# RF.net
KiCad netlist of a schematic drawn in Altium Designer
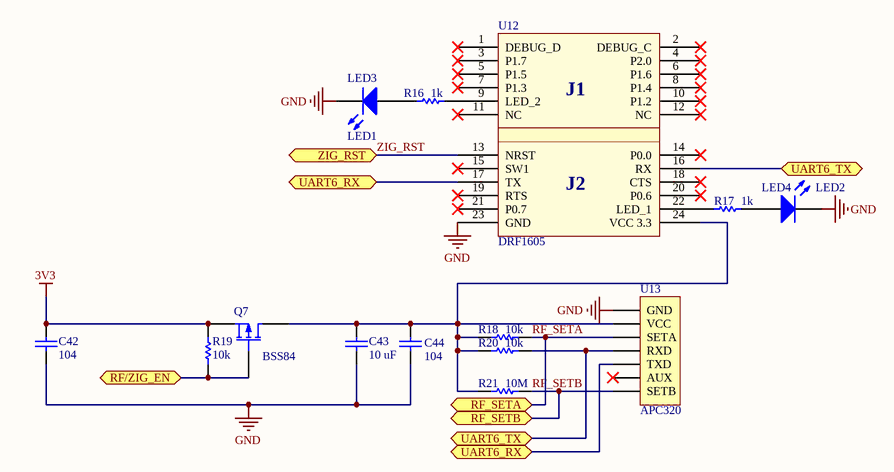
[diagram p0: RF.SchDoc]

(export (version "E")
  (design (tool "Eeschema 10.0.6"))
  (components
    (comp (ref "C42")
      (value "104")
      (footprint "C0603")
      (description "CAP CER 0.1UF 16V Y5V 0402")
      (fields
        (field (name "MANUFACTURER") "Yageo")
        (field (name "DIGI-KEY PART NUMBER") "311-1047-1-ND")
        (field (name "PUBLISHER") "Altium Limited")
      )
      (libsource (lib "RobotClub") (part "Cap_SMT"))
    )
    (comp (ref "C43")
      (value "10 uF")
      (footprint "C1210")
      (description "CAP CER 0.1UF 16V Y5V 0402")
      (fields
        (field (name "MANUFACTURER") "Yageo")
        (field (name "DIGI-KEY PART NUMBER") "311-1047-1-ND")
        (field (name "PUBLISHER") "Altium Limited")
      )
      (libsource (lib "RobotClub") (part "Cap_SMT"))
    )
    (comp (ref "C44")
      (value "104")
      (footprint "C0603")
      (description "CAP CER 0.1UF 16V Y5V 0402")
      (fields
        (field (name "MANUFACTURER") "Yageo")
        (field (name "DIGI-KEY PART NUMBER") "311-1047-1-ND")
        (field (name "PUBLISHER") "Altium Limited")
      )
      (libsource (lib "RobotClub") (part "Cap_SMT"))
    )
    (comp (ref "LED3")
      (value "LED1")
      (footprint "SM/LED_0603")
      (description "LED GREEN 0.2MM 13MCD 0402 SMD")
      (fields
        (field (name "DIGI-KEY PART NUMBER") "511-1592-2-ND")
        (field (name "MANUFACTURER") "Lite-On Inc")
        (field (name "PUBLISHER") "Altium Limited")
      )
      (libsource (lib "RobotClub") (part "LED"))
    )
    (comp (ref "LED4")
      (value "LED2")
      (footprint "SM/LED_0603")
      (description "LED GREEN 0.2MM 13MCD 0402 SMD")
      (fields
        (field (name "DIGI-KEY PART NUMBER") "511-1592-2-ND")
        (field (name "MANUFACTURER") "Lite-On Inc")
        (field (name "PUBLISHER") "Altium Limited")
      )
      (libsource (lib "RobotClub") (part "LED"))
    )
    (comp (ref "Q7")
      (value "BSS84")
      (footprint "SOT23-3")
      (description "MOSFET P-CH 50V 130MA SOT23-3")
      (fields
        (field (name "DIGI-KEY PART NUMBER") "BSS84-FDITR-ND")
        (field (name "MANUFACTURER") "Diodes Inc")
        (field (name "PUBLISHER") "Altium Limited")
      )
      (libsource (lib "RobotClub") (part "MOSFET-P GSD"))
    )
    (comp (ref "R16")
      (value "1k")
      (footprint "R0603")
      (description "Resistor SMD 5%")
      (fields
        (field (name "DIGI-KEY PART NUMBER") "P3.24KLTR-ND")
        (field (name "MANUFACTURER") "Panasonic Electronic Components")
        (field (name "PUBLISHER") "Altium Limited")
      )
      (libsource (lib "RobotClub") (part "R_SMD5"))
    )
    (comp (ref "R17")
      (value "1k")
      (footprint "R0603")
      (description "Resistor SMD 5%")
      (fields
        (field (name "DIGI-KEY PART NUMBER") "P3.24KLTR-ND")
        (field (name "MANUFACTURER") "Panasonic Electronic Components")
        (field (name "PUBLISHER") "Altium Limited")
      )
      (libsource (lib "RobotClub") (part "R_SMD5"))
    )
    (comp (ref "R18")
      (value "10k")
      (footprint "R0603")
      (description "Resistor SMD 5%")
      (fields
        (field (name "DIGI-KEY PART NUMBER") "P3.24KLTR-ND")
        (field (name "MANUFACTURER") "Panasonic Electronic Components")
        (field (name "PUBLISHER") "Altium Limited")
      )
      (libsource (lib "RobotClub") (part "R_SMD5"))
    )
    (comp (ref "R19")
      (value "10k")
      (footprint "R0603")
      (description "Resistor SMD 5%")
      (fields
        (field (name "DIGI-KEY PART NUMBER") "P3.24KLTR-ND")
        (field (name "MANUFACTURER") "Panasonic Electronic Components")
        (field (name "PUBLISHER") "Altium Limited")
      )
      (libsource (lib "RobotClub") (part "R_SMD5"))
    )
    (comp (ref "R20")
      (value "10k")
      (footprint "R0603")
      (description "Resistor SMD 5%")
      (fields
        (field (name "DIGI-KEY PART NUMBER") "P3.24KLTR-ND")
        (field (name "MANUFACTURER") "Panasonic Electronic Components")
        (field (name "PUBLISHER") "Altium Limited")
      )
      (libsource (lib "RobotClub") (part "R_SMD5"))
    )
    (comp (ref "R21")
      (value "10M")
      (footprint "R0603")
      (description "Resistor SMD 5%")
      (fields
        (field (name "DIGI-KEY PART NUMBER") "P3.24KLTR-ND")
        (field (name "MANUFACTURER") "Panasonic Electronic Components")
        (field (name "PUBLISHER") "Altium Limited")
      )
      (libsource (lib "RobotClub") (part "R_SMD5"))
    )
    (comp (ref "U12") (value "DRF1605") (footprint "DRF1605") (libsource (lib "RobotClub") (part "DRF1605")))
    (comp (ref "U13")
      (value "APC320")
      (footprint "APC320 - 2D")
      (libsource (lib "RobotClub") (part "APC320"))
    )
  )
  (nets
    (net (code "1") (name "/RF_SETA") (class "Default")
      (node (ref "R18") (pin "2") (pinfunction "2_2") (pintype "passive"))
      (node (ref "U13") (pin "3") (pinfunction "SETA_3") (pintype "passive"))
    )
    (net (code "2") (name "/RF_SETB") (class "Default")
      (node (ref "R21") (pin "2") (pinfunction "2_2") (pintype "passive"))
      (node (ref "U13") (pin "7") (pinfunction "SETB_7") (pintype "passive"))
    )
    (net (code "3") (name "/RF{slash}ZIG_EN") (class "Default")
      (node (ref "Q7") (pin "1") (pinfunction "G_1") (pintype "passive"))
      (node (ref "R19") (pin "2") (pinfunction "2_2") (pintype "passive"))
    )
    (net (code "4") (name "/UART6_RX") (class "Default")
      (node (ref "U12") (pin "17") (pinfunction "TX_17") (pintype "passive"))
      (node (ref "U13") (pin "5") (pinfunction "TXD_5") (pintype "passive"))
    )
    (net (code "5") (name "/UART6_TX") (class "Default")
      (node (ref "R20") (pin "2") (pinfunction "2_2") (pintype "passive"))
      (node (ref "U12") (pin "16") (pinfunction "RX_16") (pintype "passive"))
      (node (ref "U13") (pin "4") (pinfunction "RXD_4") (pintype "passive"))
    )
    (net (code "6") (name "/ZIG_RST") (class "Default")
      (node (ref "U12") (pin "13") (pinfunction "NRST_13") (pintype "passive"))
    )
    (net (code "7") (name "3V3") (class "Default")
      (node (ref "C42") (pin "2") (pinfunction "2_2") (pintype "passive"))
      (node (ref "Q7") (pin "2") (pinfunction "S_2") (pintype "passive"))
      (node (ref "R19") (pin "1") (pinfunction "1_1") (pintype "passive"))
    )
    (net (code "8") (name "GND") (class "Default")
      (node (ref "C42") (pin "1") (pinfunction "1_1") (pintype "passive"))
      (node (ref "C43") (pin "1") (pinfunction "1_1") (pintype "passive"))
      (node (ref "C44") (pin "1") (pinfunction "1_1") (pintype "passive"))
      (node (ref "LED3") (pin "2") (pinfunction "K_2") (pintype "passive"))
      (node (ref "LED4") (pin "2") (pinfunction "K_2") (pintype "passive"))
      (node (ref "U12") (pin "23") (pinfunction "GND_23") (pintype "passive"))
      (node (ref "U13") (pin "1") (pinfunction "GND_1") (pintype "passive"))
    )
    (net (code "9") (name "Net-(LED3-A)") (class "Default")
      (node (ref "LED3") (pin "1") (pinfunction "A_1") (pintype "passive"))
      (node (ref "R16") (pin "1") (pinfunction "1_1") (pintype "passive"))
    )
    (net (code "10") (name "Net-(LED4-A)") (class "Default")
      (node (ref "LED4") (pin "1") (pinfunction "A_1") (pintype "passive"))
      (node (ref "R17") (pin "2") (pinfunction "2_2") (pintype "passive"))
    )
    (net (code "11") (name "Net-(Q7-D)") (class "Default")
      (node (ref "C43") (pin "2") (pinfunction "2_2") (pintype "passive"))
      (node (ref "C44") (pin "2") (pinfunction "2_2") (pintype "passive"))
      (node (ref "Q7") (pin "3") (pinfunction "D_3") (pintype "passive"))
      (node (ref "R18") (pin "1") (pinfunction "1_1") (pintype "passive"))
      (node (ref "R20") (pin "1") (pinfunction "1_1") (pintype "passive"))
      (node (ref "R21") (pin "1") (pinfunction "1_1") (pintype "passive"))
      (node (ref "U12") (pin "24") (pinfunction "VCC_3.3_24") (pintype "passive"))
      (node (ref "U13") (pin "2") (pinfunction "VCC_2") (pintype "passive"))
    )
    (net (code "12") (name "Net-(U12-LED_1)") (class "Default")
      (node (ref "R17") (pin "1") (pinfunction "1_1") (pintype "passive"))
      (node (ref "U12") (pin "22") (pinfunction "LED_1_22") (pintype "passive"))
    )
    (net (code "13") (name "Net-(U12-LED_2)") (class "Default")
      (node (ref "R16") (pin "2") (pinfunction "2_2") (pintype "passive"))
      (node (ref "U12") (pin "9") (pinfunction "LED_2_9") (pintype "passive"))
    )
    (net (code "14") (name "unconnected-(U12-CTS-Pad18)") (class "Default")
      (node (ref "U12") (pin "18") (pinfunction "CTS_18") (pintype "passive+no_connect"))
    )
    (net (code "15") (name "unconnected-(U12-DEBUG_C-Pad2)") (class "Default")
      (node (ref "U12") (pin "2") (pinfunction "DEBUG_C_2") (pintype "passive+no_connect"))
    )
    (net (code "16") (name "unconnected-(U12-DEBUG_D-Pad1)") (class "Default")
      (node (ref "U12") (pin "1") (pinfunction "DEBUG_D_1") (pintype "passive+no_connect"))
    )
    (net (code "17") (name "unconnected-(U12-NC-Pad11)") (class "Default")
      (node (ref "U12") (pin "11") (pinfunction "NC_11") (pintype "passive+no_connect"))
    )
    (net (code "18") (name "unconnected-(U12-NC-Pad12)") (class "Default")
      (node (ref "U12") (pin "12") (pinfunction "NC_12") (pintype "passive+no_connect"))
    )
    (net (code "19") (name "unconnected-(U12-P0.0-Pad14)") (class "Default")
      (node (ref "U12") (pin "14") (pinfunction "P0.0_14") (pintype "passive+no_connect"))
    )
    (net (code "20") (name "unconnected-(U12-P0.6-Pad20)") (class "Default")
      (node (ref "U12") (pin "20") (pinfunction "P0.6_20") (pintype "passive+no_connect"))
    )
    (net (code "21") (name "unconnected-(U12-P0.7-Pad21)") (class "Default")
      (node (ref "U12") (pin "21") (pinfunction "P0.7_21") (pintype "passive+no_connect"))
    )
    (net (code "22") (name "unconnected-(U12-P1.2-Pad10)") (class "Default")
      (node (ref "U12") (pin "10") (pinfunction "P1.2_10") (pintype "passive+no_connect"))
    )
    (net (code "23") (name "unconnected-(U12-P1.3-Pad7)") (class "Default")
      (node (ref "U12") (pin "7") (pinfunction "P1.3_7") (pintype "passive+no_connect"))
    )
    (net (code "24") (name "unconnected-(U12-P1.4-Pad8)") (class "Default")
      (node (ref "U12") (pin "8") (pinfunction "P1.4_8") (pintype "passive+no_connect"))
    )
    (net (code "25") (name "unconnected-(U12-P1.5-Pad5)") (class "Default")
      (node (ref "U12") (pin "5") (pinfunction "P1.5_5") (pintype "passive+no_connect"))
    )
    (net (code "26") (name "unconnected-(U12-P1.6-Pad6)") (class "Default")
      (node (ref "U12") (pin "6") (pinfunction "P1.6_6") (pintype "passive+no_connect"))
    )
    (net (code "27") (name "unconnected-(U12-P1.7-Pad3)") (class "Default")
      (node (ref "U12") (pin "3") (pinfunction "P1.7_3") (pintype "passive+no_connect"))
    )
    (net (code "28") (name "unconnected-(U12-P2.0-Pad4)") (class "Default")
      (node (ref "U12") (pin "4") (pinfunction "P2.0_4") (pintype "passive+no_connect"))
    )
    (net (code "29") (name "unconnected-(U12-RTS-Pad19)") (class "Default")
      (node (ref "U12") (pin "19") (pinfunction "RTS_19") (pintype "passive+no_connect"))
    )
    (net (code "30") (name "unconnected-(U12-SW1-Pad15)") (class "Default")
      (node (ref "U12") (pin "15") (pinfunction "SW1_15") (pintype "passive+no_connect"))
    )
    (net (code "31") (name "unconnected-(U13-AUX-Pad6)") (class "Default")
      (node (ref "U13") (pin "6") (pinfunction "AUX_6") (pintype "passive+no_connect"))
    )
  )
)
